# chess.net
KiCad netlist of a schematic drawn in Altium Designer
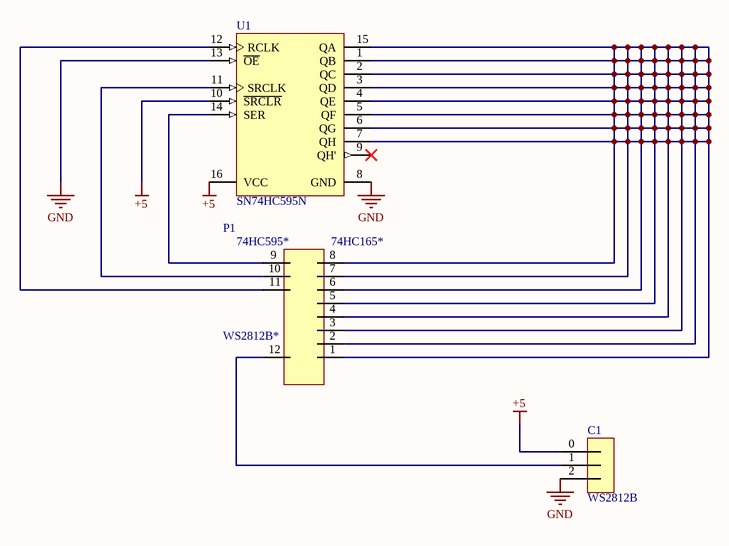
[diagram p0: chess.SchDoc]

(export (version "E")
  (design (tool "Eeschema 10.0.6"))
  (components
    (comp (ref "C1") (value "WS2812B") (libsource (lib "chess") (part "WS2812B")))
    (comp (ref "P1")
      (value "Connector")
      (description "Placeholder for arduino\r\nGPIO pins")
      (libsource (lib "chess") (part "Connector"))
    )
    (comp (ref "U1")
      (value "SN74HC595N")
      (footprint "N0016A")
      (description "8-Bit Shift Registers With 3-State Output Registers, N0016A, TUBE")
      (fields
        (field (name "GENERIC PART NUMBER") "SN74HC595")
        (field (name "MANUFACTURER") "Texas Instruments")
      )
      (libsource (lib "Altium Content Vault") (part "TI-SN74XHCT595X_SN74LV595A-16"))
    )
  )
  (nets
    (net (code "1") (name "+5") (class "Default")
      (node (ref "C1") (pin "0") (pinfunction "0_0") (pintype "passive"))
      (node (ref "U1") (pin "10") (pinfunction "~{SRCLR}_10") (pintype "input"))
      (node (ref "U1") (pin "16") (pinfunction "VCC_16") (pintype "power_in"))
    )
    (net (code "2") (name "GND") (class "Default")
      (node (ref "C1") (pin "2") (pinfunction "2_2") (pintype "passive"))
      (node (ref "U1") (pin "13") (pinfunction "~{OE}_13") (pintype "input"))
      (node (ref "U1") (pin "8") (pinfunction "GND_8") (pintype "power_in"))
    )
    (net (code "3") (name "Net-(C1-Pad1)") (class "Default")
      (node (ref "C1") (pin "1") (pinfunction "1_1") (pintype "passive"))
      (node (ref "P1") (pin "12") (pinfunction "12_12") (pintype "passive"))
    )
    (net (code "4") (name "Net-(U1-QA)") (class "Default")
      (node (ref "P1") (pin "1") (pinfunction "1_1") (pintype "passive"))
      (node (ref "P1") (pin "2") (pinfunction "2_2") (pintype "passive"))
      (node (ref "P1") (pin "3") (pinfunction "3_3") (pintype "passive"))
      (node (ref "P1") (pin "4") (pinfunction "4_4") (pintype "passive"))
      (node (ref "P1") (pin "5") (pinfunction "5_5") (pintype "passive"))
      (node (ref "P1") (pin "6") (pinfunction "6_6") (pintype "passive"))
      (node (ref "P1") (pin "7") (pinfunction "7_7") (pintype "passive"))
      (node (ref "P1") (pin "8") (pinfunction "8_8") (pintype "passive"))
      (node (ref "U1") (pin "1") (pinfunction "QB_1") (pintype "tri_state"))
      (node (ref "U1") (pin "15") (pinfunction "QA_15") (pintype "tri_state"))
      (node (ref "U1") (pin "2") (pinfunction "QC_2") (pintype "tri_state"))
      (node (ref "U1") (pin "3") (pinfunction "QD_3") (pintype "tri_state"))
      (node (ref "U1") (pin "4") (pinfunction "QE_4") (pintype "tri_state"))
      (node (ref "U1") (pin "5") (pinfunction "QF_5") (pintype "tri_state"))
      (node (ref "U1") (pin "6") (pinfunction "QG_6") (pintype "tri_state"))
      (node (ref "U1") (pin "7") (pinfunction "QH_7") (pintype "tri_state"))
    )
    (net (code "5") (name "Net-(U1-RCLK)") (class "Default")
      (node (ref "P1") (pin "11") (pinfunction "11_11") (pintype "passive"))
      (node (ref "U1") (pin "12") (pinfunction "RCLK_12") (pintype "input"))
    )
    (net (code "6") (name "Net-(U1-SER)") (class "Default")
      (node (ref "P1") (pin "9") (pinfunction "9_9") (pintype "passive"))
      (node (ref "U1") (pin "14") (pinfunction "SER_14") (pintype "input"))
    )
    (net (code "7") (name "Net-(U1-SRCLK)") (class "Default")
      (node (ref "P1") (pin "10") (pinfunction "10_10") (pintype "passive"))
      (node (ref "U1") (pin "11") (pinfunction "SRCLK_11") (pintype "input"))
    )
    (net (code "8") (name "unconnected-(U1-QH'-Pad9)") (class "Default")
      (node (ref "U1") (pin "9") (pinfunction "QH'_9") (pintype "output+no_connect"))
    )
  )
)
